# PowerConnections.net
KiCad netlist of a schematic drawn in Altium Designer
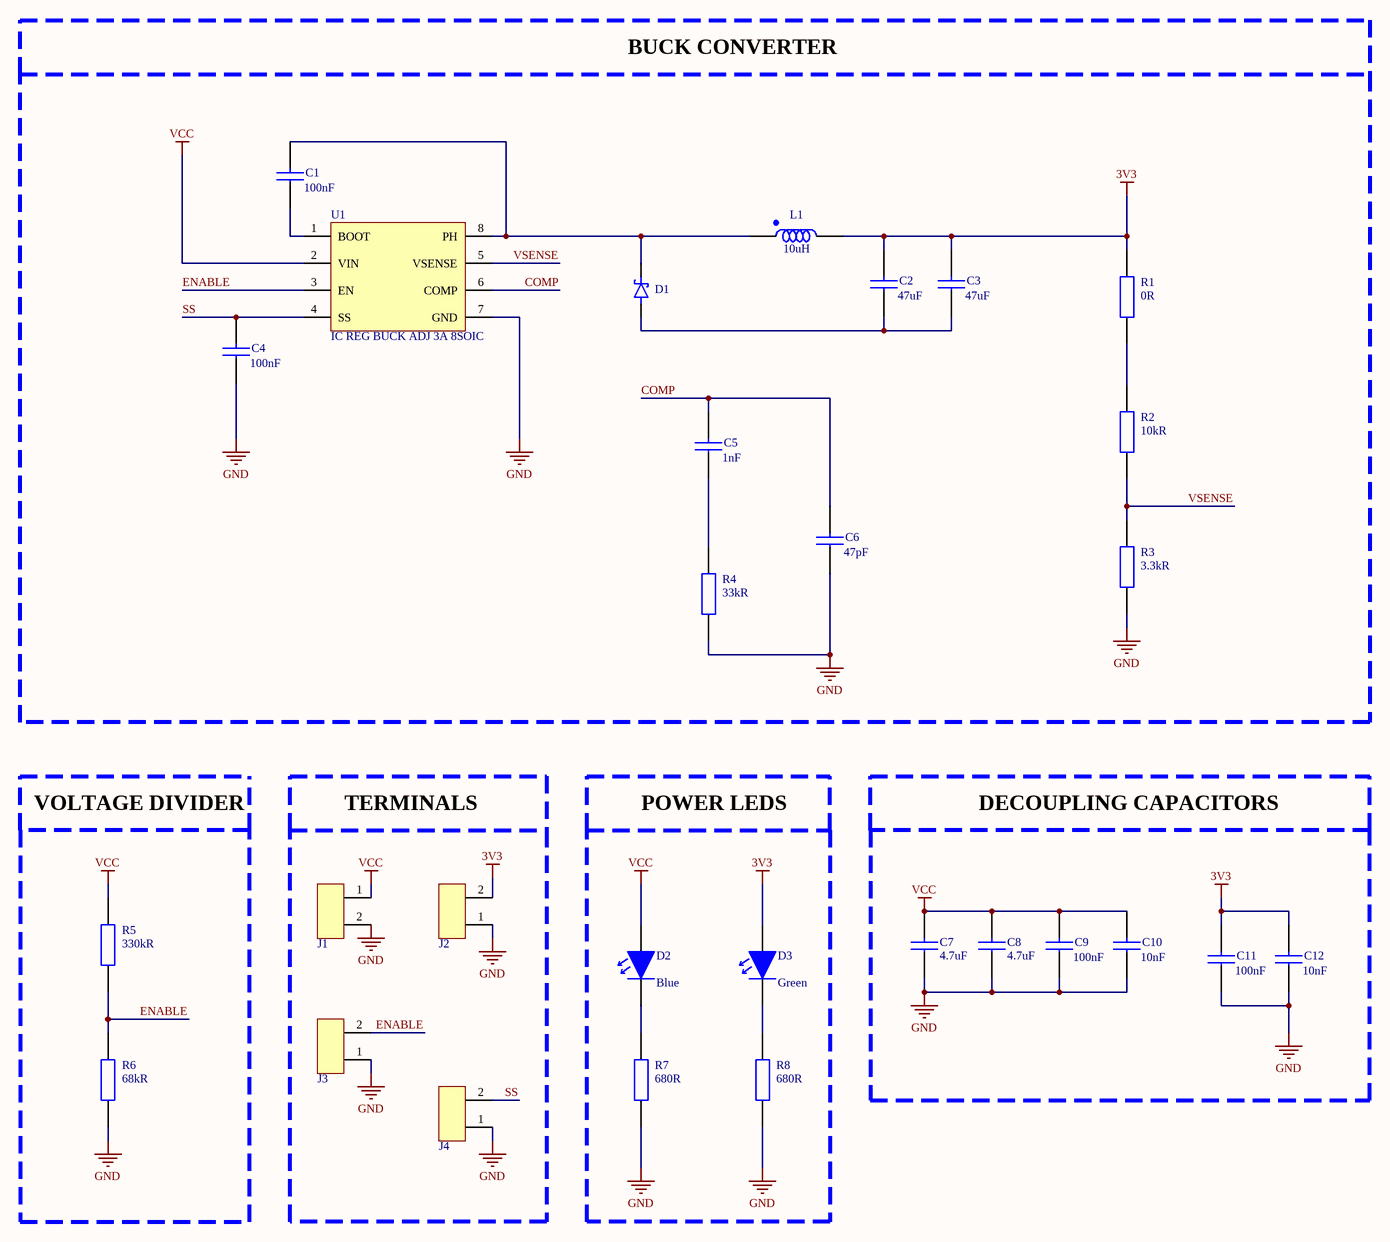
[diagram p0: PowerConnections.SchDoc]

(export (version "E")
  (design (tool "Eeschema 10.0.6"))
  (components
    (comp (ref "C1")
      (value "C1206C104J5RAC7800")
      (footprint "CAP_1206")
      (description "CAP CER 0.1UF 50V X7R 1206")
      (fields
        (field (name "MANUFACTURER") "Kyocera AVX")
        (field (name "MANUFACTURER PART NUMBER") "12065C104JAT2A")
        (field (name "CAPACITANCE") "100nF")
        (field (name "DESIGNEDBY") "Aslı Kurt")
      )
      (libsource (lib "Capacitors") (part "CAP CER 100nF 1206"))
    )
    (comp (ref "C2")
      (value "GMC31X5R476M25NT")
      (footprint "CAP_1206")
      (description "CAP CER 47UF 25V X5R 1206")
      (fields
        (field (name "MANUFACTURER") "Cal-Chip Electronics")
        (field (name "TOLERANCE") "20%")
        (field (name "CAPACITANCE") "47uF")
        (field (name "DESIGNEDBY") "Aslı Kurt")
      )
      (libsource (lib "Capacitors") (part "CAP CER 47uF 1206"))
    )
    (comp (ref "C3")
      (value "GMC31X5R476M25NT")
      (footprint "CAP_1206")
      (description "CAP CER 47UF 25V X5R 1206")
      (fields
        (field (name "MANUFACTURER") "Cal-Chip Electronics")
        (field (name "TOLERANCE") "20%")
        (field (name "CAPACITANCE") "47uF")
        (field (name "DESIGNEDBY") "Aslı Kurt")
      )
      (libsource (lib "Capacitors") (part "CAP CER 47uF 1206"))
    )
    (comp (ref "C4")
      (value "C1206C104J5RAC7800")
      (footprint "CAP_1206")
      (description "CAP CER 0.1UF 50V X7R 1206")
      (fields
        (field (name "MANUFACTURER") "Kyocera AVX")
        (field (name "MANUFACTURER PART NUMBER") "12065C104JAT2A")
        (field (name "CAPACITANCE") "100nF")
        (field (name "DESIGNEDBY") "Aslı Kurt")
      )
      (libsource (lib "Capacitors") (part "CAP CER 100nF 1206"))
    )
    (comp (ref "C5")
      (value "C3216C0G2J102J085AA")
      (footprint "CAP_1206")
      (description "CAP CER 1nF 1206")
      (fields
        (field (name "MANUFACTURER") "TDK")
        (field (name "CAPACITANCE") "1nF")
        (field (name "DESIGNEDBY") "Aslı Kurt")
      )
      (libsource (lib "Capacitors") (part "CAP CER 1nF 1206"))
    )
    (comp (ref "C6")
      (value "C1206C470J5GAC7800")
      (footprint "CAP_1206")
      (description "CAP CER 47PF 50V C0G/NP0 1206")
      (fields
        (field (name "MANUFACTURER") "KEMET")
        (field (name "MANUFACTURER PART NUMBER") "C1206C470J5GACTU")
        (field (name "CAPACITANCE") "47pF")
      )
      (libsource (lib "Capacitors") (part "CAP CER 47pF 1206"))
    )
    (comp (ref "C7")
      (value "CL21A475KAQNNNE")
      (footprint "CAP_0805")
      (description "CAP CER 4.7uF %10 0805")
      (fields
        (field (name "MANUFACTURER") "Samsung")
        (field (name "TOLERANCE") "10%")
        (field (name "CAPACITANCE") "4.7uF")
        (field (name "DESIGNED BY") "BERK")
      )
      (libsource (lib "Capacitors") (part "CAP CER 4.7uF 0805"))
    )
    (comp (ref "C8")
      (value "CL21A475KAQNNNE")
      (footprint "CAP_0805")
      (description "CAP CER 4.7uF %10 0805")
      (fields
        (field (name "MANUFACTURER") "Samsung")
        (field (name "TOLERANCE") "10%")
        (field (name "CAPACITANCE") "4.7uF")
        (field (name "DESIGNED BY") "BERK")
      )
      (libsource (lib "Capacitors") (part "CAP CER 4.7uF 0805"))
    )
    (comp (ref "C9")
      (value "C1206C104J5RAC7800")
      (footprint "CAP_1206")
      (description "CAP CER 0.1UF 50V X7R 1206")
      (fields
        (field (name "MANUFACTURER") "Kyocera AVX")
        (field (name "MANUFACTURER PART NUMBER") "12065C104JAT2A")
        (field (name "CAPACITANCE") "100nF")
        (field (name "DESIGNEDBY") "Aslı Kurt")
      )
      (libsource (lib "Capacitors") (part "CAP CER 100nF 1206"))
    )
    (comp (ref "C10")
      (value "C3216C0G2J103J160AA")
      (footprint "CAP_1206")
      (description "CAP CER 10nF 1206")
      (fields
        (field (name "MANUFACTURER") "TDK")
        (field (name "CAPACITANCE") "10nF")
        (field (name "DESIGNEDBY") "Aslı Kurt")
      )
      (libsource (lib "Capacitors") (part "CAP CER 10nF 1206"))
    )
    (comp (ref "C11")
      (value "C1206C104J5RAC7800")
      (footprint "CAP_1206")
      (description "CAP CER 0.1UF 50V X7R 1206")
      (fields
        (field (name "MANUFACTURER") "Kyocera AVX")
        (field (name "MANUFACTURER PART NUMBER") "12065C104JAT2A")
        (field (name "CAPACITANCE") "100nF")
        (field (name "DESIGNEDBY") "Aslı Kurt")
      )
      (libsource (lib "Capacitors") (part "CAP CER 100nF 1206"))
    )
    (comp (ref "C12")
      (value "C3216C0G2J103J160AA")
      (footprint "CAP_1206")
      (description "CAP CER 10nF 1206")
      (fields
        (field (name "MANUFACTURER") "TDK")
        (field (name "CAPACITANCE") "10nF")
        (field (name "DESIGNEDBY") "Aslı Kurt")
      )
      (libsource (lib "Capacitors") (part "CAP CER 10nF 1206"))
    )
    (comp (ref "D1")
      (value "B340AE-13")
      (footprint "SMA")
      (description "Rectifier Diode Schottky 40V 3A 2-Pin SMA T/R")
      (fields (field (name "MANUFACTURER") "Diodes") (field (name "DESIGNEDBY") "Aslı Kurt"))
      (libsource (lib "Diodes") (part "B340A"))
    )
    (comp (ref "D2")
      (value "150120BS75000")
      (footprint "LED_BLUE_1206")
      (description "Led, Blue, 470 Nm, 3.2 V, 30 Ma, 145 Mcd Rohs Compliant: Yes ¦Wurth Elektronik 150120BS75000")
      (fields
        (field (name "MANUFACTURER") "Wurth Electronics")
        (field (name "COLOR") "Blue")
        (field (name "DESIGNEDBY") "Aslı Kurt")
      )
      (libsource (lib "Diodes") (part "LED BLUE 1206"))
    )
    (comp (ref "D3")
      (value "150120GS75000")
      (footprint "LED_GREEN_1206")
      (description "WL-SMCW SMT Mono-Color Chip LED Waterclear")
      (fields
        (field (name "MANUFACTURER") "Wurth Electronics")
        (field (name "COLOR") "Green")
        (field (name "DESIGNEDBY") "Aslı Kurt")
      )
      (libsource (lib "Diodes") (part "LED GREEN 1206"))
    )
    (comp (ref "J1")
      (value "282836-2")
      (footprint "TERMINAL")
      (description "Connector, Terminal Block; Wire Receptacle; 2 Pos.; 16-30 AWG; 0.197 in. CL; Sid")
      (fields
        (field (name "MANUFACTURER") "TE Connectivity")
        (field (name "VOLTAGE") "300V")
        (field (name "DESIGNED BY") "Aslı Kurt")
      )
      (libsource (lib "") (part "2x1 TERMINAL 5mm_1"))
    )
    (comp (ref "J2")
      (value "282836-2")
      (footprint "TERMINAL")
      (description "Connector, Terminal Block; Wire Receptacle; 2 Pos.; 16-30 AWG; 0.197 in. CL; Sid")
      (fields
        (field (name "MANUFACTURER") "TE Connectivity")
        (field (name "VOLTAGE") "300V")
        (field (name "DESIGNED BY") "Aslı Kurt")
      )
      (libsource (lib "Connectors") (part "2x1 TERMINAL 5mm"))
    )
    (comp (ref "J3")
      (value "2x1 Male Header 2.54mm")
      (footprint "2x1 Male Header 2.54mm")
      (libsource (lib "Connectors") (part "2x1 Male Header 2.54mm"))
    )
    (comp (ref "J4")
      (value "2x1 Male Header 2.54mm")
      (footprint "2x1 Male Header 2.54mm")
      (libsource (lib "Connectors") (part "2x1 Male Header 2.54mm"))
    )
    (comp (ref "L1")
      (value "SRI1004")
      (footprint "IND_1010")
      (description "10uH 10X10 4.8A - SMD Güç Bobini - SRI1004")
      (fields
        (field (name "TOLERANCE") "20%")
        (field (name "INDUCTANCE") "10uH")
        (field (name "DESIGNEDBY") "Aslı Kurt")
      )
      (libsource (lib "Inductors") (part "IND 10uH"))
    )
    (comp (ref "R1")
      (value "PMR18EZPJ000")
      (footprint "RES_1206")
      (description "Res Thick Film 1206 0 Ohm 5% Molded SMD Paper T/R")
      (fields
        (field (name "MANUFACTURER") "Rohm")
        (field (name "RESISTANCE") "0R")
        (field (name "DESIGNEDBY") "Aslı Kurt")
      )
      (libsource (lib "Resistors") (part "RES 0 OHM 1206"))
    )
    (comp (ref "R2")
      (value "RC1206JR-0710KL")
      (footprint "RES_1206")
      (description "RES 10K OHM 5% 1/4W 1206")
      (fields
        (field (name "MANUFACTURER") "Yageo")
        (field (name "TOLERANCE") "5%")
        (field (name "RESISTANCE") "10kR")
        (field (name "DESIGNEDBY") "Aslı Kurt")
      )
      (libsource (lib "Resistors") (part "RES 10K OHM 1206"))
    )
    (comp (ref "R3")
      (value "RC1206JR-073K3L")
      (footprint "RES_1206")
      (description "RES 3.3K OHM 5% 1/4W 1206")
      (fields
        (field (name "MANUFACTURER") "Yageo")
        (field (name "RESISTANCE") "3.3kR")
        (field (name "DESIGNEDBY") "Aslı Kurt")
      )
      (libsource (lib "Resistors") (part "RES 3K3 OHM 1206"))
    )
    (comp (ref "R4")
      (value "RES 33K OHM 5% 1/4W 1206")
      (footprint "RES_1206")
      (description "SMD Chip Resistor, 33 kOhm, ï¿½ 5%, 250 mW, 1206 [3216 Metric], Thick Film, General Purpose")
      (fields
        (field (name "MANUFACTURER") "Yageo")
        (field (name "MANUFACTURER PART NUMBER") "RC1206JR-0733KL")
        (field (name "RESISTANCE") "33kR")
        (field (name "DESIGNEDBY") "Aslı Kurt")
      )
      (libsource (lib "Resistors") (part "RES 33K OHM 1206"))
    )
    (comp (ref "R5")
      (value "RES 330K OHM 5% 1/4W 1206")
      (footprint "RES_1206")
      (fields
        (field (name "MANUFACTURER") "Yageo")
        (field (name "MANUFACTURER PART NUMBER") "RC1206JR-07330KL")
        (field (name "RESISTANCE") "330kR")
        (field (name "DESIGNEDBY") "Aslı Kurt")
      )
      (libsource (lib "Resistors") (part "RES 330K OHM 1206"))
    )
    (comp (ref "R6")
      (value "RES 68K OHM 5% 1/4W 1206")
      (footprint "RES_1206")
      (fields
        (field (name "MANUFACTURER") "Yageo")
        (field (name "MANUFACTURER PART NUMBER") "RC1206JR-0768KL")
        (field (name "RESISTANCE") "68kR")
        (field (name "DESIGNEDBY") "Aslı Kurt")
      )
      (libsource (lib "Resistors") (part "RES 68K OHM 1206"))
    )
    (comp (ref "R7")
      (value "RC1206FR-07680RL")
      (footprint "RES_1206")
      (description "SMD Chip Resistor, 680 Ohm, ï¿½ 1%, 250 mW, 1206 [3216 Metric], Thick Film, General Purpose")
      (fields
        (field (name "MANUFACTURER") "Yageo")
        (field (name "RESISTANCE") "680R")
        (field (name "DESIGNEDBY") "Aslı Kurt")
      )
      (libsource (lib "Resistors") (part "RES 680 OHM 1206"))
    )
    (comp (ref "R8")
      (value "RC1206FR-07680RL")
      (footprint "RES_1206")
      (description "SMD Chip Resistor, 680 Ohm, ï¿½ 1%, 250 mW, 1206 [3216 Metric], Thick Film, General Purpose")
      (fields
        (field (name "MANUFACTURER") "Yageo")
        (field (name "RESISTANCE") "680R")
        (field (name "DESIGNEDBY") "Aslı Kurt")
      )
      (libsource (lib "Resistors") (part "RES 680 OHM 1206"))
    )
    (comp (ref "U1")
      (value "IC REG BUCK ADJ 3A 8SOIC")
      (footprint "SOIC8_PAD")
      (description "3.5V to 28V Input, 3A, 570kHz Step-Down Converter with Eco-mode 8-SOIC -40 to 150")
      (fields
        (field (name "MANUFACTURER") "Texas Instruments")
        (field (name "MANUFACTURER PART NUMBER") "TPS54331DR")
        (field (name "DESIGNEDBY") "Aslı Kurt")
      )
      (libsource (lib "Regulators") (part "TPS54331DR"))
    )
  )
  (nets
    (net (code "1") (name "/COMP") (class "Default")
      (node (ref "C5") (pin "2") (pinfunction "2_2") (pintype "passive"))
      (node (ref "C6") (pin "2") (pinfunction "2_2") (pintype "passive"))
      (node (ref "U1") (pin "6") (pinfunction "COMP_6") (pintype "passive"))
    )
    (net (code "2") (name "/ENABLE") (class "Default")
      (node (ref "J3") (pin "2") (pinfunction "2_2") (pintype "power_in"))
      (node (ref "R5") (pin "1") (pinfunction "1_1") (pintype "passive"))
      (node (ref "R6") (pin "2") (pinfunction "2_2") (pintype "passive"))
      (node (ref "U1") (pin "3") (pinfunction "EN_3") (pintype "passive"))
    )
    (net (code "3") (name "/SS") (class "Default")
      (node (ref "C4") (pin "2") (pinfunction "2_2") (pintype "passive"))
      (node (ref "J4") (pin "2") (pinfunction "2_2") (pintype "power_in"))
      (node (ref "U1") (pin "4") (pinfunction "SS_4") (pintype "passive"))
    )
    (net (code "4") (name "/VSENSE") (class "Default")
      (node (ref "R2") (pin "1") (pinfunction "1_1") (pintype "passive"))
      (node (ref "R3") (pin "2") (pinfunction "2_2") (pintype "passive"))
      (node (ref "U1") (pin "5") (pinfunction "VSENSE_5") (pintype "passive"))
    )
    (net (code "5") (name "3V3") (class "Default")
      (node (ref "C11") (pin "2") (pinfunction "2_2") (pintype "passive"))
      (node (ref "C12") (pin "2") (pinfunction "2_2") (pintype "passive"))
      (node (ref "C2") (pin "2") (pinfunction "2_2") (pintype "passive"))
      (node (ref "C3") (pin "2") (pinfunction "2_2") (pintype "passive"))
      (node (ref "D3") (pin "2") (pinfunction "2_2") (pintype "power_in"))
      (node (ref "J2") (pin "2") (pinfunction "2_2") (pintype "passive"))
      (node (ref "L1") (pin "2") (pinfunction "2_2") (pintype "passive"))
      (node (ref "R1") (pin "2") (pinfunction "2_2") (pintype "passive"))
    )
    (net (code "6") (name "GND") (class "Default")
      (node (ref "C10") (pin "1") (pinfunction "1_1") (pintype "passive"))
      (node (ref "C11") (pin "1") (pinfunction "1_1") (pintype "passive"))
      (node (ref "C12") (pin "1") (pinfunction "1_1") (pintype "passive"))
      (node (ref "C4") (pin "1") (pinfunction "1_1") (pintype "passive"))
      (node (ref "C6") (pin "1") (pinfunction "1_1") (pintype "passive"))
      (node (ref "C7") (pin "1") (pinfunction "1_1") (pintype "passive"))
      (node (ref "C8") (pin "1") (pinfunction "1_1") (pintype "passive"))
      (node (ref "C9") (pin "1") (pinfunction "1_1") (pintype "passive"))
      (node (ref "J1") (pin "2") (pinfunction "2_2") (pintype "passive"))
      (node (ref "J2") (pin "1") (pinfunction "1_1") (pintype "passive"))
      (node (ref "J3") (pin "1") (pinfunction "1_1") (pintype "power_in"))
      (node (ref "J4") (pin "1") (pinfunction "1_1") (pintype "power_in"))
      (node (ref "R3") (pin "1") (pinfunction "1_1") (pintype "passive"))
      (node (ref "R4") (pin "1") (pinfunction "1_1") (pintype "passive"))
      (node (ref "R6") (pin "1") (pinfunction "1_1") (pintype "passive"))
      (node (ref "R7") (pin "1") (pinfunction "1_1") (pintype "passive"))
      (node (ref "R8") (pin "1") (pinfunction "1_1") (pintype "passive"))
      (node (ref "U1") (pin "7") (pinfunction "GND_7") (pintype "passive"))
    )
    (net (code "7") (name "Net-(C2-Pad1)") (class "Default")
      (node (ref "C2") (pin "1") (pinfunction "1_1") (pintype "passive"))
      (node (ref "C3") (pin "1") (pinfunction "1_1") (pintype "passive"))
      (node (ref "D1") (pin "1") (pinfunction "1_1") (pintype "passive"))
    )
    (net (code "8") (name "Net-(C5-Pad1)") (class "Default")
      (node (ref "C5") (pin "1") (pinfunction "1_1") (pintype "passive"))
      (node (ref "R4") (pin "2") (pinfunction "2_2") (pintype "passive"))
    )
    (net (code "9") (name "Net-(D2-Pad1)") (class "Default")
      (node (ref "D2") (pin "1") (pinfunction "1_1") (pintype "power_in"))
      (node (ref "R7") (pin "2") (pinfunction "2_2") (pintype "passive"))
    )
    (net (code "10") (name "Net-(D3-Pad1)") (class "Default")
      (node (ref "D3") (pin "1") (pinfunction "1_1") (pintype "power_in"))
      (node (ref "R8") (pin "2") (pinfunction "2_2") (pintype "passive"))
    )
    (net (code "11") (name "Net-(R1-Pad1)") (class "Default")
      (node (ref "R1") (pin "1") (pinfunction "1_1") (pintype "passive"))
      (node (ref "R2") (pin "2") (pinfunction "2_2") (pintype "passive"))
    )
    (net (code "12") (name "Net-(U1-BOOT)") (class "Default")
      (node (ref "C1") (pin "1") (pinfunction "1_1") (pintype "passive"))
      (node (ref "U1") (pin "1") (pinfunction "BOOT_1") (pintype "passive"))
    )
    (net (code "13") (name "Net-(U1-PH)") (class "Default")
      (node (ref "C1") (pin "2") (pinfunction "2_2") (pintype "passive"))
      (node (ref "D1") (pin "2") (pinfunction "2_2") (pintype "passive"))
      (node (ref "L1") (pin "1") (pinfunction "1_1") (pintype "passive"))
      (node (ref "U1") (pin "8") (pinfunction "PH_8") (pintype "passive"))
    )
    (net (code "14") (name "VCC") (class "Default")
      (node (ref "C10") (pin "2") (pinfunction "2_2") (pintype "passive"))
      (node (ref "C7") (pin "2") (pinfunction "2_2") (pintype "passive"))
      (node (ref "C8") (pin "2") (pinfunction "2_2") (pintype "passive"))
      (node (ref "C9") (pin "2") (pinfunction "2_2") (pintype "passive"))
      (node (ref "D2") (pin "2") (pinfunction "2_2") (pintype "power_in"))
      (node (ref "J1") (pin "1") (pinfunction "1_1") (pintype "passive"))
      (node (ref "R5") (pin "2") (pinfunction "2_2") (pintype "passive"))
      (node (ref "U1") (pin "2") (pinfunction "VIN_2") (pintype "passive"))
    )
  )
)
